# pwm_channel.net
KiCad netlist of a schematic drawn in Altium Designer
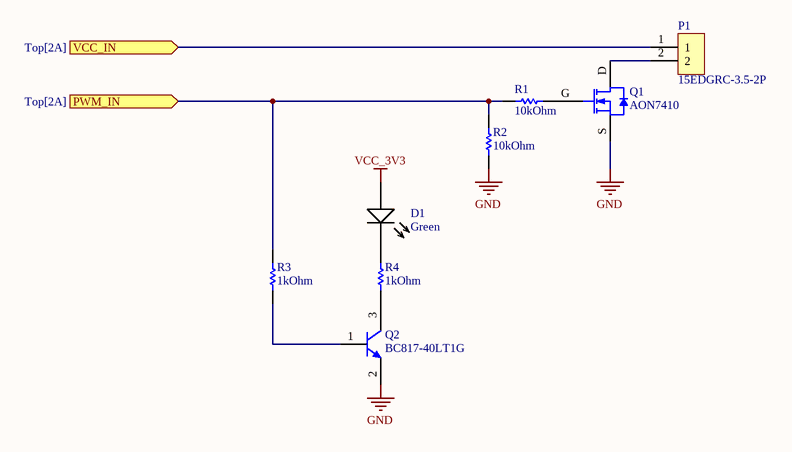
[diagram p0: pwm_channel.SchDoc]

(export (version "E")
  (design (tool "Eeschema 10.0.6"))
  (components
    (comp (ref "D1")
      (value "C205450")
      (footprint "LED_0603")
      (description "Generic LED diode SMD Green")
      (fields (field (name "COLOUR") "Green"))
      (libsource (lib "MY_LIB") (part "LED diode"))
    )
    (comp (ref "P1")
      (value "15EDGRC-3.5-2P")
      (footprint "15EDGRC-3.5 - 2 pin")
      (description "15EDGRC-3.5 - 2 pin")
      (libsource (lib "MY_LIB") (part "15EDGRC-3.5-2P"))
    )
    (comp (ref "Q1")
      (value "AON7410")
      (footprint "DFN3x3_8L")
      (description "Tranzystor MOSFET kanał N")
      (libsource (lib "MY_LIB") (part "AON7410"))
    )
    (comp (ref "Q2")
      (value "BC817-40LT1G")
      (footprint "SOT-23A")
      (description "General Purpose Transistor, NPN Silicon, 3-Pin SOT-23, Pb-Free, Tape and Reel")
      (fields (field (name "MANUFACTURER") "On Semiconductor"))
      (libsource (lib "MY_LIB") (part "BC817-40LT1G"))
    )
    (comp (ref "R1")
      (value "0603 10kOhm 1%")
      (footprint "RES_0603")
      (description "Generic Resistor SMD")
      (fields (field (name "RESISTANCE") "10kOhm"))
      (libsource (lib "MY_LIB") (part "Resistor SMD_1"))
    )
    (comp (ref "R2")
      (value "0603 10kOhm 1%")
      (footprint "RES_0603")
      (description "Generic Resistor SMD")
      (fields (field (name "RESISTANCE") "10kOhm"))
      (libsource (lib "MY_LIB") (part "Resistor SMD_1"))
    )
    (comp (ref "R3")
      (value "0603 1kOhm 1%")
      (footprint "RES_0603")
      (description "Generic Resistor SMD")
      (fields (field (name "RESISTANCE") "1kOhm"))
      (libsource (lib "MY_LIB") (part "Resistor SMD_1"))
    )
    (comp (ref "R4")
      (value "0603 1kOhm 1%")
      (footprint "RES_0603")
      (description "Generic Resistor SMD")
      (fields (field (name "RESISTANCE") "1kOhm"))
      (libsource (lib "MY_LIB") (part "Resistor SMD_1"))
    )
  )
  (nets
    (net (code "1") (name "/PWM_IN") (class "Default")
      (node (ref "R1") (pin "2") (pinfunction "2_2") (pintype "passive"))
      (node (ref "R2") (pin "1") (pinfunction "1_1") (pintype "passive"))
      (node (ref "R3") (pin "2") (pinfunction "2_2") (pintype "passive"))
    )
    (net (code "2") (name "/VCC_IN") (class "Default")
      (node (ref "P1") (pin "1") (pinfunction "1_1") (pintype "passive"))
    )
    (net (code "3") (name "GND") (class "Default")
      (node (ref "Q1") (pin "S") (pinfunction "S_S") (pintype "passive"))
      (node (ref "Q2") (pin "2") (pinfunction "E_2") (pintype "passive"))
      (node (ref "R2") (pin "2") (pinfunction "2_2") (pintype "passive"))
    )
    (net (code "4") (name "Net-(D1-PadC)") (class "Default")
      (node (ref "D1") (pin "C") (pinfunction "C_C") (pintype "passive"))
      (node (ref "R4") (pin "2") (pinfunction "2_2") (pintype "passive"))
    )
    (net (code "5") (name "Net-(P1-Pad2)") (class "Default")
      (node (ref "P1") (pin "2") (pinfunction "2_2") (pintype "passive"))
      (node (ref "Q1") (pin "D") (pinfunction "D_D") (pintype "passive"))
    )
    (net (code "6") (name "Net-(Q1-PadG)") (class "Default")
      (node (ref "Q1") (pin "G") (pinfunction "G_G") (pintype "passive"))
      (node (ref "R1") (pin "1") (pinfunction "1_1") (pintype "passive"))
    )
    (net (code "7") (name "Net-(Q2-C)") (class "Default")
      (node (ref "Q2") (pin "3") (pinfunction "C_3") (pintype "passive"))
      (node (ref "R4") (pin "1") (pinfunction "1_1") (pintype "passive"))
    )
    (net (code "8") (name "Net-(Q2-Pad1)") (class "Default")
      (node (ref "Q2") (pin "1") (pinfunction "1_1") (pintype "passive"))
      (node (ref "R3") (pin "1") (pinfunction "1_1") (pintype "passive"))
    )
    (net (code "9") (name "VCC_3V3") (class "Default")
      (node (ref "D1") (pin "A") (pinfunction "A_A") (pintype "passive"))
    )
  )
)
